# omnibothub-power-one-usb.net
KiCad netlist of a schematic drawn in Altium Designer
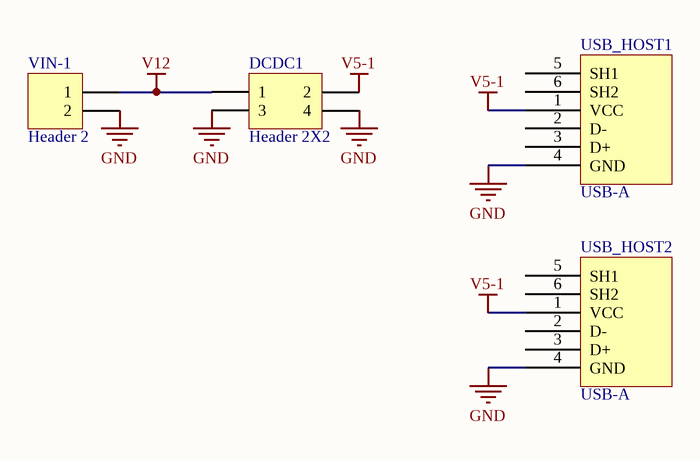
[diagram p0: omnibothub-power-one-usb.SchDoc]

(export (version "E")
  (design (tool "Eeschema 10.0.6"))
  (components
    (comp (ref "DCDC1")
      (value "Header 2X2")
      (footprint "DCDC-1")
      (description "Header, 2-Pin, Dual row")
      (fields (field (name "PUBLISHER") "Altium Limited"))
      (libsource (lib "Miscellaneous Connectors") (part "Header 2X2"))
    )
    (comp (ref "USB_HOST1")
      (value "USB-A")
      (footprint "614004135023")
      (libsource (lib "ATK-DNESP32SB") (part "USB-A"))
    )
    (comp (ref "USB_HOST2")
      (value "USB-A")
      (footprint "614004135023")
      (libsource (lib "ATK-DNESP32SB") (part "USB-A"))
    )
    (comp (ref "VIN-1")
      (value "Header 2")
      (footprint "AMASS-XT30PW-M")
      (description "Header, 2-Pin")
      (fields (field (name "PUBLISHER") "Altium Limited"))
      (libsource (lib "Miscellaneous Connectors") (part "Header 2"))
    )
  )
  (nets
    (net (code "1") (name "GND") (class "Default")
      (node (ref "DCDC1") (pin "3") (pinfunction "3_3") (pintype "passive"))
      (node (ref "DCDC1") (pin "4") (pinfunction "4_4") (pintype "passive"))
      (node (ref "USB_HOST1") (pin "4") (pinfunction "GND_4") (pintype "passive"))
      (node (ref "USB_HOST2") (pin "4") (pinfunction "GND_4") (pintype "passive"))
      (node (ref "VIN-1") (pin "2") (pinfunction "2_2") (pintype "passive"))
    )
    (net (code "2") (name "V5-1") (class "Default")
      (node (ref "DCDC1") (pin "2") (pinfunction "2_2") (pintype "passive"))
      (node (ref "USB_HOST1") (pin "1") (pinfunction "VCC_1") (pintype "passive"))
      (node (ref "USB_HOST2") (pin "1") (pinfunction "VCC_1") (pintype "passive"))
    )
    (net (code "3") (name "V12") (class "Default")
      (node (ref "DCDC1") (pin "1") (pinfunction "1_1") (pintype "passive"))
      (node (ref "VIN-1") (pin "1") (pinfunction "1_1") (pintype "passive"))
    )
    (net (code "4") (name "unconnected-(USB_HOST1-D+-Pad3)") (class "Default")
      (node (ref "USB_HOST1") (pin "3") (pinfunction "D+_3") (pintype "passive"))
    )
    (net (code "5") (name "unconnected-(USB_HOST1-D--Pad2)") (class "Default")
      (node (ref "USB_HOST1") (pin "2") (pinfunction "D-_2") (pintype "passive"))
    )
    (net (code "6") (name "unconnected-(USB_HOST1-SH1-Pad5)") (class "Default")
      (node (ref "USB_HOST1") (pin "5") (pinfunction "SH1_5") (pintype "passive"))
    )
    (net (code "7") (name "unconnected-(USB_HOST1-SH2-Pad6)") (class "Default")
      (node (ref "USB_HOST1") (pin "6") (pinfunction "SH2_6") (pintype "passive"))
    )
    (net (code "8") (name "unconnected-(USB_HOST2-D+-Pad3)") (class "Default")
      (node (ref "USB_HOST2") (pin "3") (pinfunction "D+_3") (pintype "passive"))
    )
    (net (code "9") (name "unconnected-(USB_HOST2-D--Pad2)") (class "Default")
      (node (ref "USB_HOST2") (pin "2") (pinfunction "D-_2") (pintype "passive"))
    )
    (net (code "10") (name "unconnected-(USB_HOST2-SH1-Pad5)") (class "Default")
      (node (ref "USB_HOST2") (pin "5") (pinfunction "SH1_5") (pintype "passive"))
    )
    (net (code "11") (name "unconnected-(USB_HOST2-SH2-Pad6)") (class "Default")
      (node (ref "USB_HOST2") (pin "6") (pinfunction "SH2_6") (pintype "passive"))
    )
  )
)
